# Bike_sharing_system_final_one_with_30_pi.net
KiCad netlist of a schematic drawn in EasyEDA
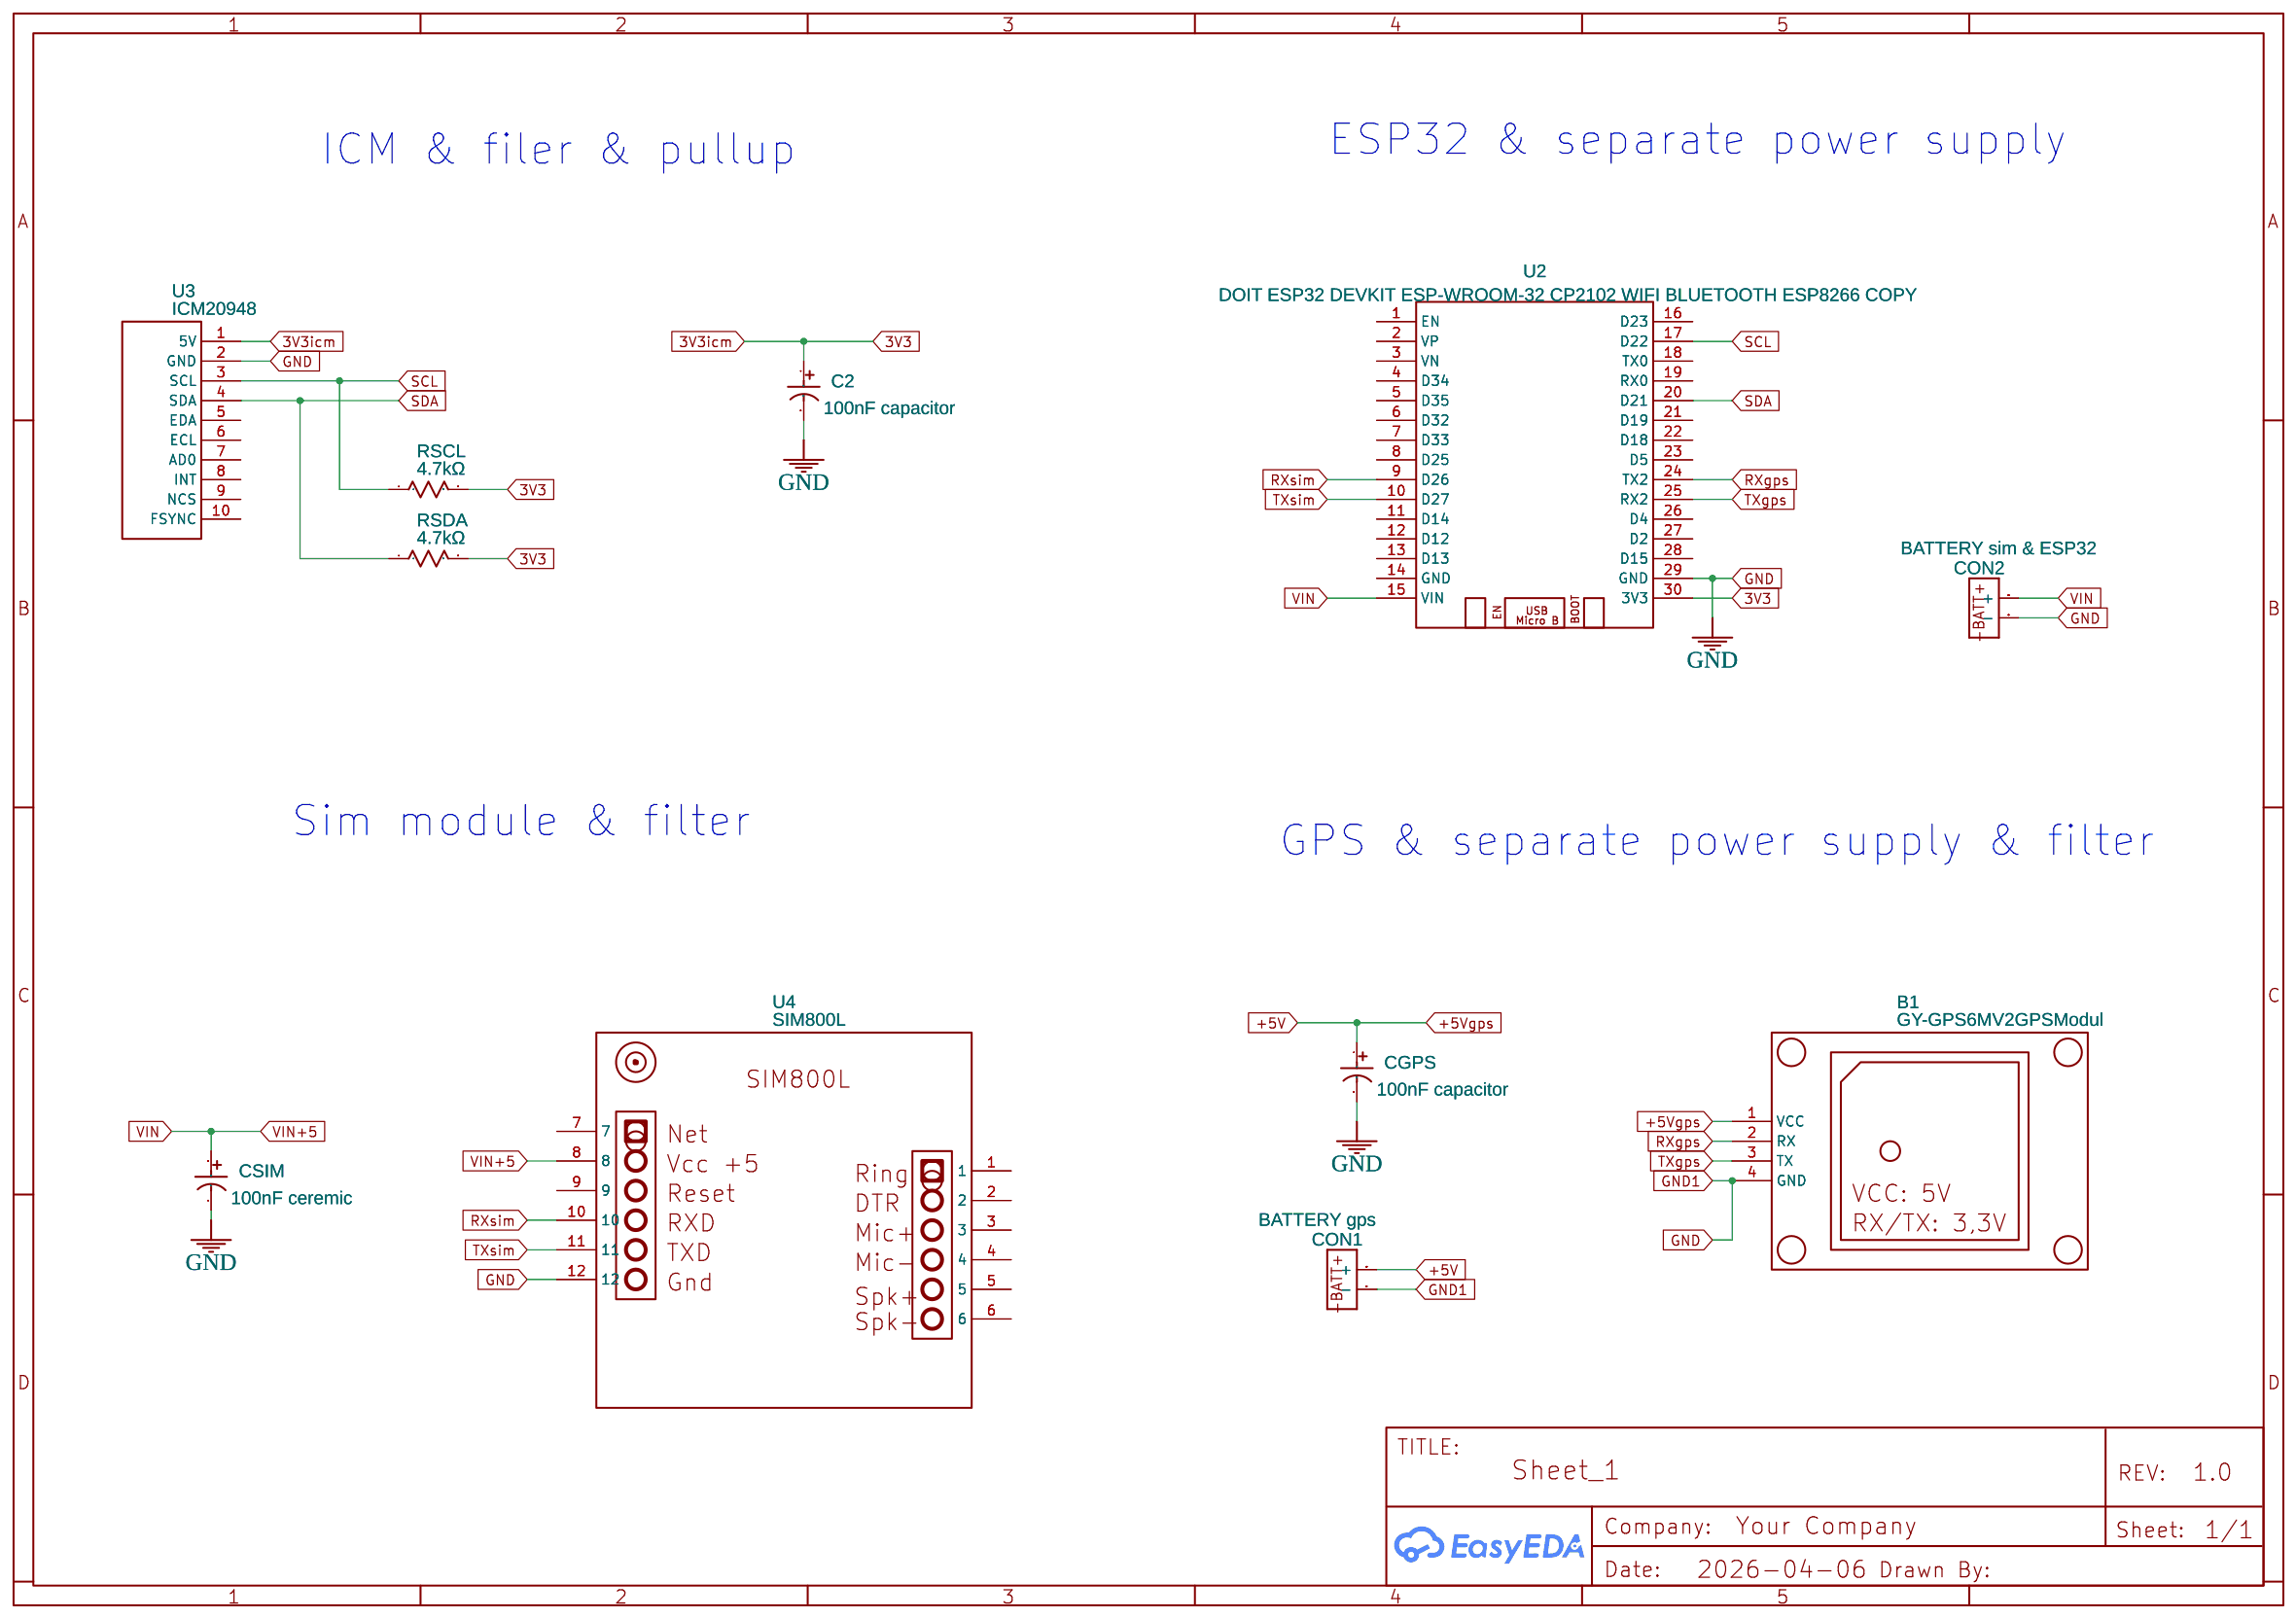
[diagram p0: schematic sheet]

(export (version "E")
  (design (tool "Eeschema 10.0.6"))
  (components
    (comp (ref "B1") (value "GY-GPS6MV2GPSModul") (libsource (lib "") (part "GY-GPS6MV2GPSModul")))
    (comp (ref "C2")
      (value "100nF capacitor")
      (fields
        (field (name "Manufacturer Part") "KM476M016D11RR0VH2FP0")
        (field (name "Manufacturer") "CX(承兴)")
      )
      (libsource (lib "") (part "CAPACITOR 680UF COPY_1"))
    )
    (comp (ref "CGPS")
      (value "100nF capacitor")
      (fields
        (field (name "Manufacturer Part") "KM476M016D11RR0VH2FP0")
        (field (name "Manufacturer") "CX(承兴)")
      )
      (libsource (lib "") (part "CAPACITOR 680UF COPY"))
    )
    (comp (ref "CON1") (value "BATTERY gps") (libsource (lib "") (part "2 PIN CON (BATTERY)")))
    (comp (ref "CON2") (value "BATTERY sim & ESP32") (libsource (lib "") (part "2 PIN CON (BATTERY)")))
    (comp (ref "CSIM")
      (value "100nF ceremic")
      (fields
        (field (name "Manufacturer Part") "KM476M016D11RR0VH2FP0")
        (field (name "Manufacturer") "CX(承兴)")
      )
      (libsource (lib "") (part "CAPACITOR 680UF COPY_2"))
    )
    (comp (ref "RSCL")
      (value "4.7kΩ")
      (fields (field (name "Manufacturer Part") "Resister"))
      (libsource (lib "") (part "RESISTER COPY"))
    )
    (comp (ref "RSDA")
      (value "4.7kΩ")
      (fields (field (name "Manufacturer Part") "Resister"))
      (libsource (lib "") (part "RESISTER COPY_1"))
    )
    (comp (ref "U2")
      (value "DOIT ESP32 DEVKIT ESP-WROOM-32 CP2102 WIFI BLUETOOTH ESP8266 COPY")
      (libsource (lib "") (part "DOIT ESP32 DEVKIT ESP-WROOM-32 CP2102 WIFI BLUETOOTH ESP8266 COPY"))
    )
    (comp (ref "U3") (value "ICM20948") (libsource (lib "") (part "ICM20948")))
    (comp (ref "U4") (value "SIM800L") (libsource (lib "") (part "SIM800L")))
  )
  (nets
    (net (code "1") (name "+5V") (class "Default")
      (node (ref "B1") (pin "1") (pinfunction "VCC_1") (pintype "unspecified"))
      (node (ref "CGPS") (pin "1") (pinfunction "1_1") (pintype "unspecified"))
      (node (ref "CON1") (pin "BAT+") (pinfunction "+_BAT+") (pintype "unspecified"))
    )
    (net (code "2") (name "3V3") (class "Default")
      (node (ref "C2") (pin "1") (pinfunction "1_1") (pintype "unspecified"))
      (node (ref "RSCL") (pin "2") (pinfunction "2_2") (pintype "unspecified"))
      (node (ref "RSDA") (pin "2") (pinfunction "2_2") (pintype "unspecified"))
      (node (ref "U2") (pin "30") (pinfunction "3V3_30") (pintype "bidirectional"))
      (node (ref "U3") (pin "1") (pinfunction "5V_1") (pintype "unspecified"))
    )
    (net (code "3") (name "GND") (class "Default")
      (node (ref "B1") (pin "4") (pinfunction "GND_4") (pintype "unspecified"))
      (node (ref "C2") (pin "2") (pinfunction "2_2") (pintype "unspecified"))
      (node (ref "CGPS") (pin "2") (pinfunction "2_2") (pintype "unspecified"))
      (node (ref "CON1") (pin "BAT-") (pinfunction "-_BAT-") (pintype "unspecified"))
      (node (ref "CON2") (pin "BAT-") (pinfunction "-_BAT-") (pintype "unspecified"))
      (node (ref "CSIM") (pin "2") (pinfunction "2_2") (pintype "unspecified"))
      (node (ref "U2") (pin "29") (pinfunction "GND_29") (pintype "bidirectional"))
      (node (ref "U3") (pin "2") (pinfunction "GND_2") (pintype "unspecified"))
      (node (ref "U4") (pin "12") (pinfunction "12_12") (pintype "unspecified"))
    )
    (net (code "4") (name "RXgps") (class "Default")
      (node (ref "B1") (pin "2") (pinfunction "RX_2") (pintype "unspecified"))
      (node (ref "U2") (pin "24") (pinfunction "TX2_24") (pintype "bidirectional"))
    )
    (net (code "5") (name "RXsim") (class "Default")
      (node (ref "U2") (pin "9") (pinfunction "D26_9") (pintype "bidirectional"))
      (node (ref "U4") (pin "10") (pinfunction "10_10") (pintype "unspecified"))
    )
    (net (code "6") (name "SCL") (class "Default")
      (node (ref "RSCL") (pin "1") (pinfunction "1_1") (pintype "unspecified"))
      (node (ref "U2") (pin "17") (pinfunction "D22_17") (pintype "bidirectional"))
      (node (ref "U3") (pin "3") (pinfunction "SCL_3") (pintype "unspecified"))
    )
    (net (code "7") (name "SDA") (class "Default")
      (node (ref "RSDA") (pin "1") (pinfunction "1_1") (pintype "unspecified"))
      (node (ref "U2") (pin "20") (pinfunction "D21_20") (pintype "bidirectional"))
      (node (ref "U3") (pin "4") (pinfunction "SDA_4") (pintype "unspecified"))
    )
    (net (code "8") (name "TXgps") (class "Default")
      (node (ref "B1") (pin "3") (pinfunction "TX_3") (pintype "unspecified"))
      (node (ref "U2") (pin "25") (pinfunction "RX2_25") (pintype "bidirectional"))
    )
    (net (code "9") (name "TXsim") (class "Default")
      (node (ref "U2") (pin "10") (pinfunction "D27_10") (pintype "bidirectional"))
      (node (ref "U4") (pin "11") (pinfunction "11_11") (pintype "unspecified"))
    )
    (net (code "10") (name "VIN") (class "Default")
      (node (ref "CON2") (pin "BAT+") (pinfunction "+_BAT+") (pintype "unspecified"))
      (node (ref "CSIM") (pin "1") (pinfunction "1_1") (pintype "unspecified"))
      (node (ref "U2") (pin "15") (pinfunction "VIN_15") (pintype "input"))
      (node (ref "U4") (pin "8") (pinfunction "8_8") (pintype "unspecified"))
    )
    (net (code "11") (name "unconnected-(U2-D2-Pad27)") (class "Default")
      (node (ref "U2") (pin "27") (pinfunction "D2_27") (pintype "bidirectional"))
    )
    (net (code "12") (name "unconnected-(U2-D4-Pad26)") (class "Default")
      (node (ref "U2") (pin "26") (pinfunction "D4_26") (pintype "bidirectional"))
    )
    (net (code "13") (name "unconnected-(U2-D5-Pad23)") (class "Default")
      (node (ref "U2") (pin "23") (pinfunction "D5_23") (pintype "bidirectional"))
    )
    (net (code "14") (name "unconnected-(U2-D12-Pad12)") (class "Default")
      (node (ref "U2") (pin "12") (pinfunction "D12_12") (pintype "bidirectional"))
    )
    (net (code "15") (name "unconnected-(U2-D13-Pad13)") (class "Default")
      (node (ref "U2") (pin "13") (pinfunction "D13_13") (pintype "bidirectional"))
    )
    (net (code "16") (name "unconnected-(U2-D14-Pad11)") (class "Default")
      (node (ref "U2") (pin "11") (pinfunction "D14_11") (pintype "bidirectional"))
    )
    (net (code "17") (name "unconnected-(U2-D15-Pad28)") (class "Default")
      (node (ref "U2") (pin "28") (pinfunction "D15_28") (pintype "bidirectional"))
    )
    (net (code "18") (name "unconnected-(U2-D18-Pad22)") (class "Default")
      (node (ref "U2") (pin "22") (pinfunction "D18_22") (pintype "bidirectional"))
    )
    (net (code "19") (name "unconnected-(U2-D19-Pad21)") (class "Default")
      (node (ref "U2") (pin "21") (pinfunction "D19_21") (pintype "bidirectional"))
    )
    (net (code "20") (name "unconnected-(U2-D23-Pad16)") (class "Default")
      (node (ref "U2") (pin "16") (pinfunction "D23_16") (pintype "bidirectional"))
    )
    (net (code "21") (name "unconnected-(U2-D25-Pad8)") (class "Default")
      (node (ref "U2") (pin "8") (pinfunction "D25_8") (pintype "bidirectional"))
    )
    (net (code "22") (name "unconnected-(U2-D32-Pad6)") (class "Default")
      (node (ref "U2") (pin "6") (pinfunction "D32_6") (pintype "bidirectional"))
    )
    (net (code "23") (name "unconnected-(U2-D33-Pad7)") (class "Default")
      (node (ref "U2") (pin "7") (pinfunction "D33_7") (pintype "bidirectional"))
    )
    (net (code "24") (name "unconnected-(U2-D34-Pad4)") (class "Default")
      (node (ref "U2") (pin "4") (pinfunction "D34_4") (pintype "input"))
    )
    (net (code "25") (name "unconnected-(U2-D35-Pad5)") (class "Default")
      (node (ref "U2") (pin "5") (pinfunction "D35_5") (pintype "input"))
    )
    (net (code "26") (name "unconnected-(U2-EN-Pad1)") (class "Default")
      (node (ref "U2") (pin "1") (pinfunction "EN_1") (pintype "bidirectional"))
    )
    (net (code "27") (name "unconnected-(U2-GND-Pad14)") (class "Default")
      (node (ref "U2") (pin "14") (pinfunction "GND_14") (pintype "bidirectional"))
    )
    (net (code "28") (name "unconnected-(U2-RX0-Pad19)") (class "Default")
      (node (ref "U2") (pin "19") (pinfunction "RX0_19") (pintype "bidirectional"))
    )
    (net (code "29") (name "unconnected-(U2-TX0-Pad18)") (class "Default")
      (node (ref "U2") (pin "18") (pinfunction "TX0_18") (pintype "bidirectional"))
    )
    (net (code "30") (name "unconnected-(U2-VN-Pad3)") (class "Default")
      (node (ref "U2") (pin "3") (pinfunction "VN_3") (pintype "input"))
    )
    (net (code "31") (name "unconnected-(U2-VP-Pad2)") (class "Default")
      (node (ref "U2") (pin "2") (pinfunction "VP_2") (pintype "input"))
    )
    (net (code "32") (name "unconnected-(U3-AD0-Pad7)") (class "Default")
      (node (ref "U3") (pin "7") (pinfunction "AD0_7") (pintype "unspecified"))
    )
    (net (code "33") (name "unconnected-(U3-ECL-Pad6)") (class "Default")
      (node (ref "U3") (pin "6") (pinfunction "ECL_6") (pintype "unspecified"))
    )
    (net (code "34") (name "unconnected-(U3-EDA-Pad5)") (class "Default")
      (node (ref "U3") (pin "5") (pinfunction "EDA_5") (pintype "unspecified"))
    )
    (net (code "35") (name "unconnected-(U3-FSYNC-Pad10)") (class "Default")
      (node (ref "U3") (pin "10") (pinfunction "FSYNC_10") (pintype "unspecified"))
    )
    (net (code "36") (name "unconnected-(U3-INT-Pad8)") (class "Default")
      (node (ref "U3") (pin "8") (pinfunction "INT_8") (pintype "unspecified"))
    )
    (net (code "37") (name "unconnected-(U3-NCS-Pad9)") (class "Default")
      (node (ref "U3") (pin "9") (pinfunction "NCS_9") (pintype "unspecified"))
    )
    (net (code "38") (name "unconnected-(U4-Pad1)") (class "Default")
      (node (ref "U4") (pin "1") (pinfunction "1_1") (pintype "unspecified"))
    )
    (net (code "39") (name "unconnected-(U4-Pad2)") (class "Default")
      (node (ref "U4") (pin "2") (pinfunction "2_2") (pintype "unspecified"))
    )
    (net (code "40") (name "unconnected-(U4-Pad3)") (class "Default")
      (node (ref "U4") (pin "3") (pinfunction "3_3") (pintype "unspecified"))
    )
    (net (code "41") (name "unconnected-(U4-Pad4)") (class "Default")
      (node (ref "U4") (pin "4") (pinfunction "4_4") (pintype "unspecified"))
    )
    (net (code "42") (name "unconnected-(U4-Pad5)") (class "Default")
      (node (ref "U4") (pin "5") (pinfunction "5_5") (pintype "unspecified"))
    )
    (net (code "43") (name "unconnected-(U4-Pad6)") (class "Default")
      (node (ref "U4") (pin "6") (pinfunction "6_6") (pintype "unspecified"))
    )
    (net (code "44") (name "unconnected-(U4-Pad7)") (class "Default")
      (node (ref "U4") (pin "7") (pinfunction "7_7") (pintype "unspecified"))
    )
    (net (code "45") (name "unconnected-(U4-Pad9)") (class "Default")
      (node (ref "U4") (pin "9") (pinfunction "9_9") (pintype "unspecified"))
    )
  )
)
